# v_2.net
KiCad netlist of a schematic drawn in EAGLE
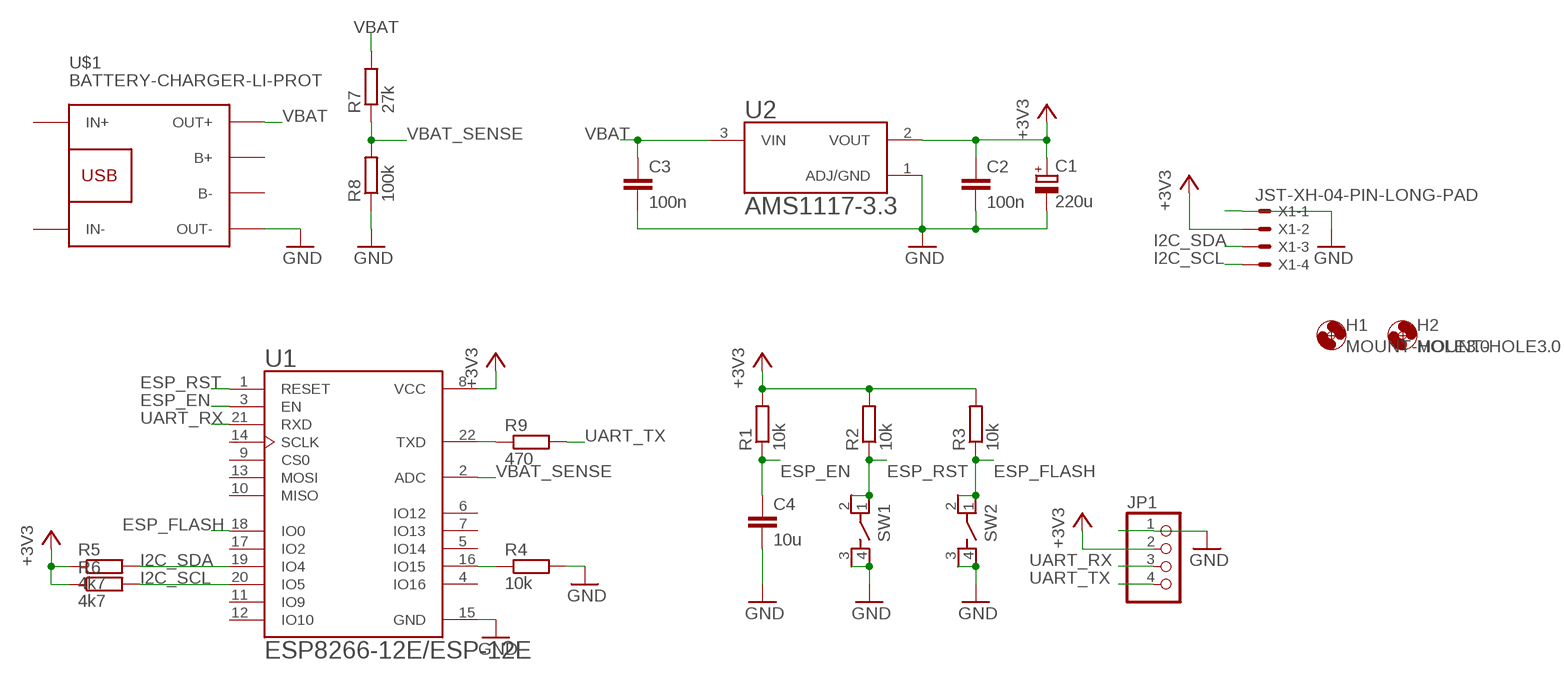
[diagram p0: schematic, sheet 1]

(export (version "E")
  (design (tool "Eeschema 10.0.6"))
  (components
    (comp (ref "C1")
      (value "220u")
      (footprint "eagle-import:153CLV-0605")
      (libsource (lib "eagle-import") (part "CPOL-EU153CLV-0605"))
    )
    (comp (ref "C2")
      (value "100n")
      (footprint "eagle-import:C0805")
      (libsource (lib "eagle-import") (part "C-EUC0805"))
    )
    (comp (ref "C3")
      (value "100n")
      (footprint "eagle-import:C0805")
      (libsource (lib "eagle-import") (part "C-EUC0805"))
    )
    (comp (ref "C4")
      (value "10u")
      (footprint "eagle-import:C0805")
      (libsource (lib "eagle-import") (part "C-EUC0805"))
    )
    (comp (ref "H1")
      (value "MOUNT-HOLE3.0")
      (footprint "eagle-import:3,0")
      (libsource (lib "eagle-import") (part "MOUNT-HOLE3.0"))
    )
    (comp (ref "H2")
      (value "MOUNT-HOLE3.0")
      (footprint "eagle-import:3,0")
      (libsource (lib "eagle-import") (part "MOUNT-HOLE3.0"))
    )
    (comp (ref "JP1")
      (value "PINHD-1X4")
      (footprint "eagle-import:1X04")
      (libsource (lib "eagle-import") (part "PINHD-1X4"))
    )
    (comp (ref "R1")
      (value "10k")
      (footprint "eagle-import:R0805")
      (libsource (lib "eagle-import") (part "R-EU_R0805"))
    )
    (comp (ref "R2")
      (value "10k")
      (footprint "eagle-import:R0805")
      (libsource (lib "eagle-import") (part "R-EU_R0805"))
    )
    (comp (ref "R3")
      (value "10k")
      (footprint "eagle-import:R0805")
      (libsource (lib "eagle-import") (part "R-EU_R0805"))
    )
    (comp (ref "R4")
      (value "10k")
      (footprint "eagle-import:R0805")
      (libsource (lib "eagle-import") (part "R-EU_R0805"))
    )
    (comp (ref "R5")
      (value "4k7")
      (footprint "eagle-import:R0805")
      (libsource (lib "eagle-import") (part "R-EU_R0805"))
    )
    (comp (ref "R6")
      (value "4k7")
      (footprint "eagle-import:R0805")
      (libsource (lib "eagle-import") (part "R-EU_R0805"))
    )
    (comp (ref "R7")
      (value "27k")
      (footprint "eagle-import:R0805")
      (libsource (lib "eagle-import") (part "R-EU_R0805"))
    )
    (comp (ref "R8")
      (value "100k")
      (footprint "eagle-import:R0805")
      (libsource (lib "eagle-import") (part "R-EU_R0805"))
    )
    (comp (ref "R9")
      (value "470")
      (footprint "eagle-import:R0805")
      (libsource (lib "eagle-import") (part "R-EU_R0805"))
    )
    (comp (ref "SW1")
      (value "PTS810_SJM_250_SMTR_LFS")
      (footprint "eagle-import:SW_PTS810_SJM_250_SMTR_LFS")
      (fields (field (name "MF") "C&K") (field (name "MP") "PTS810 SJM 250 SMTR LFS"))
      (libsource (lib "eagle-import") (part "PTS810_SJM_250_SMTR_LFS"))
    )
    (comp (ref "SW2")
      (value "PTS810_SJM_250_SMTR_LFS")
      (footprint "eagle-import:SW_PTS810_SJM_250_SMTR_LFS")
      (fields (field (name "MF") "C&K") (field (name "MP") "PTS810 SJM 250 SMTR LFS"))
      (libsource (lib "eagle-import") (part "PTS810_SJM_250_SMTR_LFS"))
    )
    (comp (ref "U$1")
      (value "BATTERY-CHARGER-LI-PROT")
      (footprint "eagle-import:BATTERY-CHARGER-LI-PROT")
      (libsource (lib "eagle-import") (part "BATTERY-CHARGER-LI-PROT"))
    )
    (comp (ref "U1")
      (value "ESP8266-12E/ESP-12E")
      (footprint "eagle-import:XCVR_ESP8266-12E_ESP-12E")
      (fields (field (name "MF") "AI-Thinker"))
      (libsource (lib "eagle-import") (part "ESP8266-12E/ESP-12E"))
    )
    (comp (ref "U2")
      (value "AMS1117-3.3")
      (footprint "eagle-import:SOT229P700X180-4N")
      (fields (field (name "MF") "Advanced Monolithic Systems"))
      (libsource (lib "eagle-import") (part "AMS1117-3.3"))
    )
    (comp (ref "X1")
      (value "JST-XH-04-PIN-LONG-PAD")
      (footprint "eagle-import:JST-XH-04-PACKAGE-LONG-PAD")
      (libsource (lib "eagle-import") (part "JST-XH-04-PIN-LONG-PAD"))
    )
  )
  (nets
    (net (code "1") (name "+3V3") (class "Default")
      (node (ref "C1") (pin "+") (pinfunction "+_+") (pintype "passive"))
      (node (ref "C2") (pin "1") (pinfunction "1_1") (pintype "passive"))
      (node (ref "JP1") (pin "2") (pinfunction "2_2") (pintype "passive"))
      (node (ref "R1") (pin "2") (pinfunction "2_2") (pintype "passive"))
      (node (ref "R2") (pin "2") (pinfunction "2_2") (pintype "passive"))
      (node (ref "R3") (pin "2") (pinfunction "2_2") (pintype "passive"))
      (node (ref "R5") (pin "1") (pinfunction "1_1") (pintype "passive"))
      (node (ref "R6") (pin "1") (pinfunction "1_1") (pintype "passive"))
      (node (ref "U1") (pin "8") (pinfunction "VCC_8") (pintype "power_in"))
      (node (ref "U2") (pin "2") (pinfunction "VOUT_2") (pintype "output"))
      (node (ref "X1") (pin "2") (pinfunction "S_2") (pintype "passive"))
    )
    (net (code "2") (name "/ESP_EN") (class "Default")
      (node (ref "C4") (pin "1") (pinfunction "1_1") (pintype "passive"))
      (node (ref "R1") (pin "1") (pinfunction "1_1") (pintype "passive"))
      (node (ref "U1") (pin "3") (pinfunction "EN_3") (pintype "input"))
    )
    (net (code "3") (name "/ESP_FLASH") (class "Default")
      (node (ref "R3") (pin "1") (pinfunction "1_1") (pintype "passive"))
      (node (ref "SW2") (pin "1") (pinfunction "1_1") (pintype "passive"))
      (node (ref "SW2") (pin "2") (pinfunction "2_2") (pintype "passive"))
      (node (ref "U1") (pin "18") (pinfunction "IO0_18") (pintype "bidirectional"))
    )
    (net (code "4") (name "/ESP_RST") (class "Default")
      (node (ref "R2") (pin "1") (pinfunction "1_1") (pintype "passive"))
      (node (ref "SW1") (pin "1") (pinfunction "1_1") (pintype "passive"))
      (node (ref "SW1") (pin "2") (pinfunction "2_2") (pintype "passive"))
      (node (ref "U1") (pin "1") (pinfunction "RESET_1") (pintype "input"))
    )
    (net (code "5") (name "/I2C_SCL") (class "Default")
      (node (ref "R6") (pin "2") (pinfunction "2_2") (pintype "passive"))
      (node (ref "U1") (pin "20") (pinfunction "IO5_20") (pintype "bidirectional"))
      (node (ref "X1") (pin "4") (pinfunction "S_4") (pintype "passive"))
    )
    (net (code "6") (name "/I2C_SDA") (class "Default")
      (node (ref "R5") (pin "2") (pinfunction "2_2") (pintype "passive"))
      (node (ref "U1") (pin "19") (pinfunction "IO4_19") (pintype "bidirectional"))
      (node (ref "X1") (pin "3") (pinfunction "S_3") (pintype "passive"))
    )
    (net (code "7") (name "/UART_RX") (class "Default")
      (node (ref "JP1") (pin "3") (pinfunction "3_3") (pintype "passive"))
      (node (ref "U1") (pin "21") (pinfunction "RXD_21") (pintype "input"))
    )
    (net (code "8") (name "/UART_TX") (class "Default")
      (node (ref "JP1") (pin "4") (pinfunction "4_4") (pintype "passive"))
      (node (ref "R9") (pin "2") (pinfunction "2_2") (pintype "passive"))
    )
    (net (code "9") (name "/VBAT") (class "Default")
      (node (ref "C3") (pin "1") (pinfunction "1_1") (pintype "passive"))
      (node (ref "R7") (pin "2") (pinfunction "2_2") (pintype "passive"))
      (node (ref "U$1") (pin "OUT+") (pinfunction "OUT+_OUT+") (pintype "bidirectional"))
      (node (ref "U2") (pin "3") (pinfunction "VIN_3") (pintype "input"))
    )
    (net (code "10") (name "/VBAT_SENSE") (class "Default")
      (node (ref "R7") (pin "1") (pinfunction "1_1") (pintype "passive"))
      (node (ref "R8") (pin "2") (pinfunction "2_2") (pintype "passive"))
      (node (ref "U1") (pin "2") (pinfunction "ADC_2") (pintype "passive"))
    )
    (net (code "11") (name "GND") (class "Default")
      (node (ref "C1") (pin "-") (pinfunction "-_-") (pintype "passive"))
      (node (ref "C2") (pin "2") (pinfunction "2_2") (pintype "passive"))
      (node (ref "C3") (pin "2") (pinfunction "2_2") (pintype "passive"))
      (node (ref "C4") (pin "2") (pinfunction "2_2") (pintype "passive"))
      (node (ref "JP1") (pin "1") (pinfunction "1_1") (pintype "passive"))
      (node (ref "R4") (pin "2") (pinfunction "2_2") (pintype "passive"))
      (node (ref "R8") (pin "1") (pinfunction "1_1") (pintype "passive"))
      (node (ref "SW1") (pin "3") (pinfunction "3_3") (pintype "passive"))
      (node (ref "SW1") (pin "4") (pinfunction "4_4") (pintype "passive"))
      (node (ref "SW2") (pin "3") (pinfunction "3_3") (pintype "passive"))
      (node (ref "SW2") (pin "4") (pinfunction "4_4") (pintype "passive"))
      (node (ref "U$1") (pin "OUT-") (pinfunction "OUT-_OUT-") (pintype "bidirectional"))
      (node (ref "U1") (pin "15") (pinfunction "GND_15") (pintype "power_in"))
      (node (ref "U2") (pin "1") (pinfunction "ADJ/GND_1") (pintype "power_in"))
      (node (ref "X1") (pin "1") (pinfunction "S_1") (pintype "passive"))
    )
    (net (code "12") (name "Net-(U1-IO15)") (class "Default")
      (node (ref "R4") (pin "1") (pinfunction "1_1") (pintype "passive"))
      (node (ref "U1") (pin "16") (pinfunction "IO15_16") (pintype "bidirectional"))
    )
    (net (code "13") (name "Net-(U1-TXD)") (class "Default")
      (node (ref "R9") (pin "1") (pinfunction "1_1") (pintype "passive"))
      (node (ref "U1") (pin "22") (pinfunction "TXD_22") (pintype "output"))
    )
    (net (code "14") (name "unconnected-(U$1-PadB+)") (class "Default")
      (node (ref "U$1") (pin "B+") (pinfunction "B+_B+") (pintype "bidirectional"))
    )
    (net (code "15") (name "unconnected-(U$1-PadB-)") (class "Default")
      (node (ref "U$1") (pin "B-") (pinfunction "B-_B-") (pintype "bidirectional"))
    )
    (net (code "16") (name "unconnected-(U$1-PadIN+)") (class "Default")
      (node (ref "U$1") (pin "IN+") (pinfunction "IN+_IN+") (pintype "bidirectional"))
    )
    (net (code "17") (name "unconnected-(U$1-PadIN-)") (class "Default")
      (node (ref "U$1") (pin "IN-") (pinfunction "IN-_IN-") (pintype "bidirectional"))
    )
    (net (code "18") (name "unconnected-(U1-CS0-Pad9)") (class "Default")
      (node (ref "U1") (pin "9") (pinfunction "CS0_9") (pintype "input"))
    )
    (net (code "19") (name "unconnected-(U1-IO2-Pad17)") (class "Default")
      (node (ref "U1") (pin "17") (pinfunction "IO2_17") (pintype "bidirectional"))
    )
    (net (code "20") (name "unconnected-(U1-IO9-Pad11)") (class "Default")
      (node (ref "U1") (pin "11") (pinfunction "IO9_11") (pintype "bidirectional"))
    )
    (net (code "21") (name "unconnected-(U1-IO10-Pad12)") (class "Default")
      (node (ref "U1") (pin "12") (pinfunction "IO10_12") (pintype "bidirectional"))
    )
    (net (code "22") (name "unconnected-(U1-IO12-Pad6)") (class "Default")
      (node (ref "U1") (pin "6") (pinfunction "IO12_6") (pintype "bidirectional"))
    )
    (net (code "23") (name "unconnected-(U1-IO13-Pad7)") (class "Default")
      (node (ref "U1") (pin "7") (pinfunction "IO13_7") (pintype "bidirectional"))
    )
    (net (code "24") (name "unconnected-(U1-IO14-Pad5)") (class "Default")
      (node (ref "U1") (pin "5") (pinfunction "IO14_5") (pintype "bidirectional"))
    )
    (net (code "25") (name "unconnected-(U1-IO16-Pad4)") (class "Default")
      (node (ref "U1") (pin "4") (pinfunction "IO16_4") (pintype "bidirectional"))
    )
    (net (code "26") (name "unconnected-(U1-MISO-Pad10)") (class "Default")
      (node (ref "U1") (pin "10") (pinfunction "MISO_10") (pintype "bidirectional"))
    )
    (net (code "27") (name "unconnected-(U1-MOSI-Pad13)") (class "Default")
      (node (ref "U1") (pin "13") (pinfunction "MOSI_13") (pintype "bidirectional"))
    )
    (net (code "28") (name "unconnected-(U1-SCLK-Pad14)") (class "Default")
      (node (ref "U1") (pin "14") (pinfunction "SCLK_14") (pintype "input"))
    )
  )
)
